# PWM_CAPTURE_VREF.net
KiCad netlist of a schematic drawn in Altium Designer
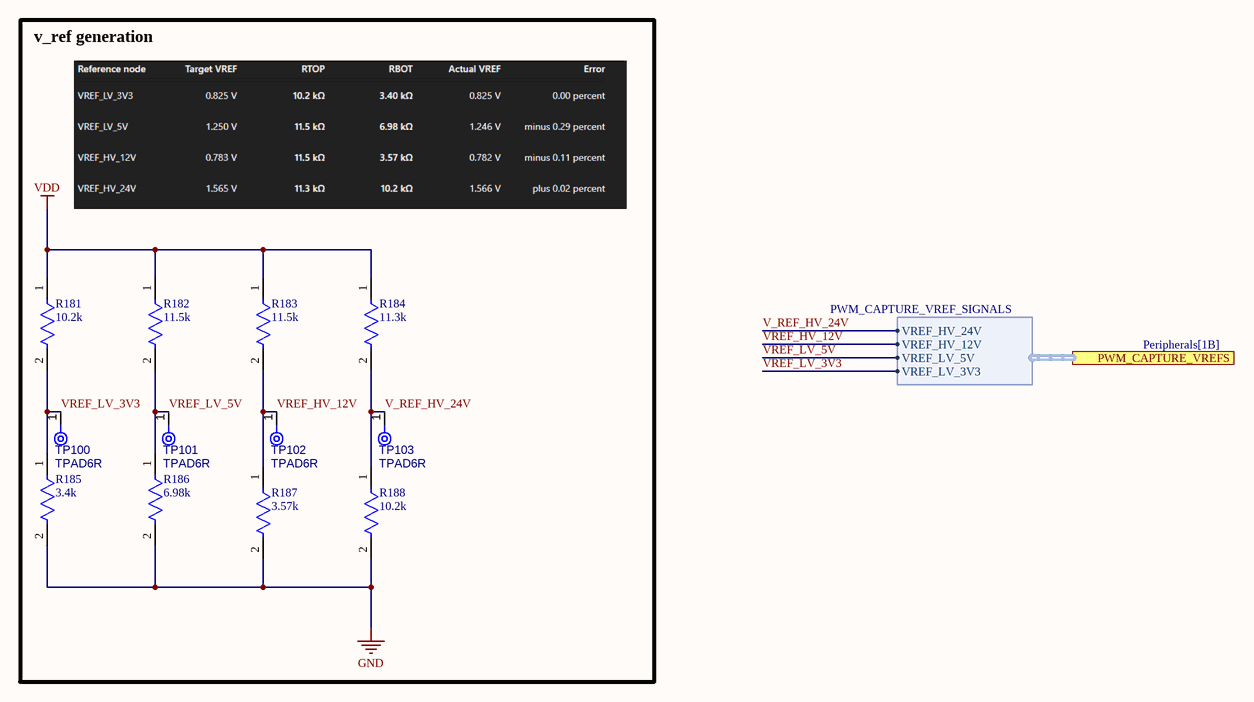
[diagram p0:  PWM_CAPTURE_VREF.SchDoc]

(export (version "E")
  (design (tool "Eeschema 10.0.6"))
  (components
    (comp (ref "R181")
      (value "10.2k")
      (footprint "FP-RT0805-MFG")
      (description "125mW Thin Film Resistor ±25ppm/℃ ±0.1% 10.2kΩ 0805 Chip Resistor - Surface Mount ROHS")
      (fields (field (name "TOLERANCE") "0.1%") (field (name "Comment") "RT0805BRD0710K2L"))
      (libsource (lib "HIL RIG FYP") (part "1029c3af85768c4190bb7ad29bc67b5"))
    )
    (comp (ref "R182")
      (value "11.5k")
      (footprint "FP-RT0603-IPC_C")
      (description "100mW Thin Film Resistor 75V ±25ppm/℃ ±0.1% 11.5kΩ 0603 Chip Resistor - Surface Mount ROHS")
      (fields (field (name "TOLERANCE") "0.1%") (field (name "Comment") "RT0603BRD0711K5L"))
      (libsource (lib "HIL RIG FYP") (part "1029c3af85768c4190bb7ad29bc67b5"))
    )
    (comp (ref "R183")
      (value "11.5k")
      (footprint "FP-RT0603-IPC_C")
      (description "100mW Thin Film Resistor 75V ±25ppm/℃ ±0.1% 11.5kΩ 0603 Chip Resistor - Surface Mount ROHS")
      (fields (field (name "TOLERANCE") "0.1%") (field (name "Comment") "RT0603BRD0711K5L"))
      (libsource (lib "HIL RIG FYP") (part "1029c3af85768c4190bb7ad29bc67b5"))
    )
    (comp (ref "R184")
      (value "11.3k")
      (footprint "FP-RT0603-IPC_C")
      (description "100mW Thin Film Resistor 75V ±25ppm/℃ ±0.1% 11.3kΩ 0603 Chip Resistor - Surface Mount ROHS")
      (fields (field (name "TOLERANCE") "0.1%") (field (name "Comment") "RT0603BRD0711K3L"))
      (libsource (lib "HIL RIG FYP") (part "1029c3af85768c4190bb7ad29bc67b5"))
    )
    (comp (ref "R185")
      (value "3.4k")
      (footprint "FP-RT0603-IPC_C")
      (description "Res Thin Film 0603 3.4K Ohm 0.1% 0.1W(1/10W) ±25ppm/C Pad SMD T/R")
      (fields (field (name "TOLERANCE") "0.1%") (field (name "Comment") "RT0603BRD073K4L"))
      (libsource (lib "HIL RIG FYP") (part "1029c3af85768c4190bb7ad29bc67b5"))
    )
    (comp (ref "R186")
      (value "6.98k")
      (footprint "FP-RT0603-IPC_C")
      (description "100mW Thin Film Resistor ±25ppm/℃ ±0.1% 6.98kΩ 0603 Chip Resistor - Surface Mount ROHS")
      (fields (field (name "TOLERANCE") "0.1%") (field (name "Comment") "RT0603BRD076K98L"))
      (libsource (lib "HIL RIG FYP") (part "1029c3af85768c4190bb7ad29bc67b5"))
    )
    (comp (ref "R187")
      (value "3.57k")
      (footprint "FP-RT0603-IPC_C")
      (description "100mW Thin Film Resistor ±25ppm/℃ ±0.1% 3.57kΩ 0603 Chip Resistor - Surface Mount ROHS")
      (fields (field (name "TOLERANCE") "0.1%") (field (name "Comment") "RT0603BRD073K57L"))
      (libsource (lib "HIL RIG FYP") (part "1029c3af85768c4190bb7ad29bc67b5"))
    )
    (comp (ref "R188")
      (value "10.2k")
      (footprint "FP-RT0805-MFG")
      (description "125mW Thin Film Resistor ±25ppm/℃ ±0.1% 10.2kΩ 0805 Chip Resistor - Surface Mount ROHS")
      (fields (field (name "TOLERANCE") "0.1%") (field (name "Comment") "RT0805BRD0710K2L"))
      (libsource (lib "HIL RIG FYP") (part "1029c3af85768c4190bb7ad29bc67b5"))
    )
    (comp (ref "TP100")
      (value "TPAD6R")
      (footprint "TP06R")
      (description "0.6mm round")
      (libsource (lib "HIL RIG FYP") (part "CMP-001-0001-4"))
    )
    (comp (ref "TP101")
      (value "TPAD6R")
      (footprint "TP06R")
      (description "0.6mm round")
      (libsource (lib "HIL RIG FYP") (part "CMP-001-0001-4"))
    )
    (comp (ref "TP102")
      (value "TPAD6R")
      (footprint "TP06R")
      (description "0.6mm round")
      (libsource (lib "HIL RIG FYP") (part "CMP-001-0001-4"))
    )
    (comp (ref "TP103")
      (value "TPAD6R")
      (footprint "TP06R")
      (description "0.6mm round")
      (libsource (lib "HIL RIG FYP") (part "CMP-001-0001-4"))
    )
  )
  (nets
    (net (code "2") (name "/VREF_HV_12V") (class "Default")
      (node (ref "R183") (pin "2") (pinfunction "2_2") (pintype "passive"))
      (node (ref "R187") (pin "1") (pinfunction "1_1") (pintype "passive"))
      (node (ref "TP102") (pin "1") (pinfunction "TP_1") (pintype "passive"))
    )
    (net (code "3") (name "/VREF_LV_3V3") (class "Default")
      (node (ref "R181") (pin "2") (pinfunction "2_2") (pintype "passive"))
      (node (ref "R185") (pin "1") (pinfunction "1_1") (pintype "passive"))
      (node (ref "TP100") (pin "1") (pinfunction "TP_1") (pintype "passive"))
    )
    (net (code "4") (name "/VREF_LV_5V") (class "Default")
      (node (ref "R182") (pin "2") (pinfunction "2_2") (pintype "passive"))
      (node (ref "R186") (pin "1") (pinfunction "1_1") (pintype "passive"))
      (node (ref "TP101") (pin "1") (pinfunction "TP_1") (pintype "passive"))
    )
    (net (code "5") (name "/V_REF_HV_24V") (class "Default")
      (node (ref "R184") (pin "2") (pinfunction "2_2") (pintype "passive"))
      (node (ref "R188") (pin "1") (pinfunction "1_1") (pintype "passive"))
      (node (ref "TP103") (pin "1") (pinfunction "TP_1") (pintype "passive"))
    )
    (net (code "7") (name "GND") (class "Default")
      (node (ref "R185") (pin "2") (pinfunction "2_2") (pintype "passive"))
      (node (ref "R186") (pin "2") (pinfunction "2_2") (pintype "passive"))
      (node (ref "R187") (pin "2") (pinfunction "2_2") (pintype "passive"))
      (node (ref "R188") (pin "2") (pinfunction "2_2") (pintype "passive"))
    )
    (net (code "8") (name "VDD") (class "Default")
      (node (ref "R181") (pin "1") (pinfunction "1_1") (pintype "passive"))
      (node (ref "R182") (pin "1") (pinfunction "1_1") (pintype "passive"))
      (node (ref "R183") (pin "1") (pinfunction "1_1") (pintype "passive"))
      (node (ref "R184") (pin "1") (pinfunction "1_1") (pintype "passive"))
    )
  )
)
